# schematic-import-source.net
KiCad netlist of a schematic drawn in EasyEDA
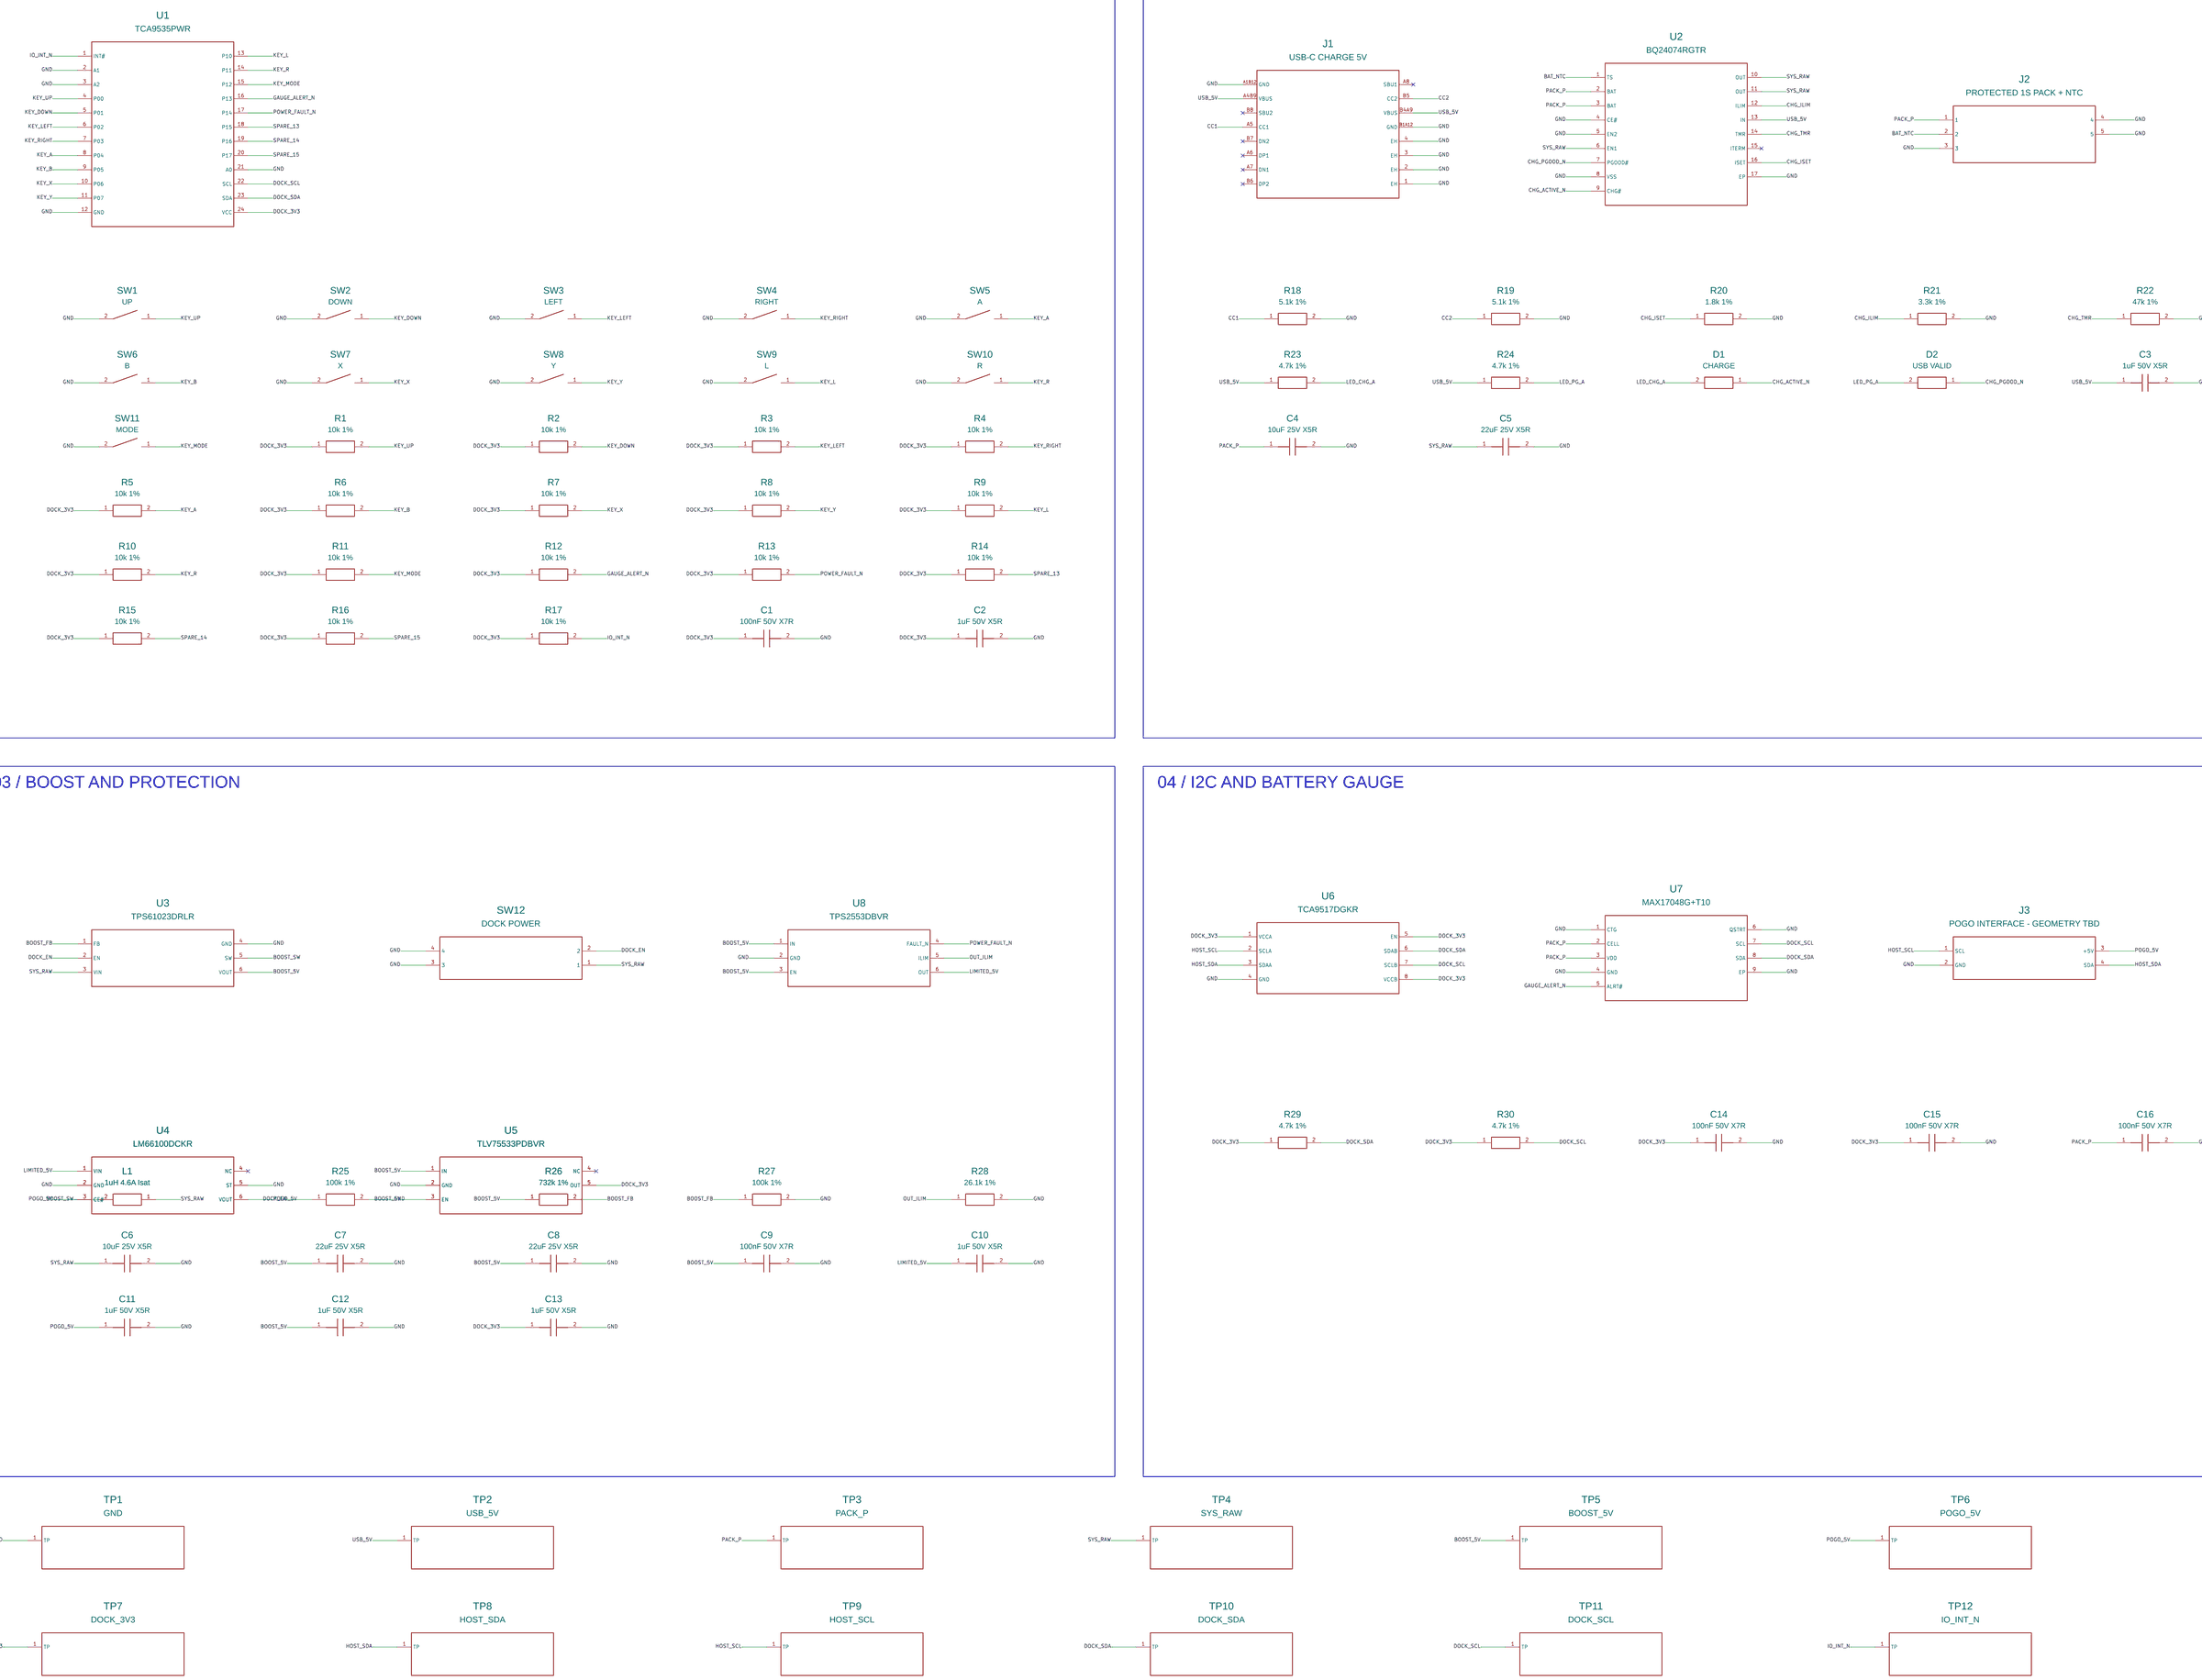
[diagram p0: schematic sheet]

(export (version "E")
  (design (tool "Eeschema 10.0.6"))
  (components
    (comp (ref "C1") (value "100nF 50V X7R") (libsource (lib "") (part "100nF 50V X7R")))
    (comp (ref "C2")
      (value "1uF 50V X5R")
      (fields
        (field (name "Manufacturer Part") "CL10A105KB8NNNC")
        (field (name "Manufacturer") "SAMSUNG(三星)")
      )
      (libsource (lib "") (part "1uF 50V X5R"))
    )
    (comp (ref "C3")
      (value "1uF 50V X5R")
      (fields
        (field (name "Manufacturer Part") "CL10A105KB8NNNC")
        (field (name "Manufacturer") "SAMSUNG(三星)")
      )
      (libsource (lib "") (part "1uF 50V X5R"))
    )
    (comp (ref "C4")
      (value "10uF 25V X5R")
      (fields
        (field (name "Manufacturer Part") "CL10A106MA8NRNC")
        (field (name "Manufacturer") "SAMSUNG(三星)")
      )
      (libsource (lib "") (part "10uF 25V X5R"))
    )
    (comp (ref "C5") (value "22uF 25V X5R") (libsource (lib "") (part "22uF 25V X5R")))
    (comp (ref "C6")
      (value "10uF 25V X5R")
      (fields
        (field (name "Manufacturer Part") "CL10A106MA8NRNC")
        (field (name "Manufacturer") "SAMSUNG(三星)")
      )
      (libsource (lib "") (part "10uF 25V X5R"))
    )
    (comp (ref "C7") (value "22uF 25V X5R") (libsource (lib "") (part "22uF 25V X5R")))
    (comp (ref "C8") (value "22uF 25V X5R") (libsource (lib "") (part "22uF 25V X5R")))
    (comp (ref "C9") (value "100nF 50V X7R") (libsource (lib "") (part "100nF 50V X7R")))
    (comp (ref "C10")
      (value "1uF 50V X5R")
      (fields
        (field (name "Manufacturer Part") "CL10A105KB8NNNC")
        (field (name "Manufacturer") "SAMSUNG(三星)")
      )
      (libsource (lib "") (part "1uF 50V X5R"))
    )
    (comp (ref "C11")
      (value "1uF 50V X5R")
      (fields
        (field (name "Manufacturer Part") "CL10A105KB8NNNC")
        (field (name "Manufacturer") "SAMSUNG(三星)")
      )
      (libsource (lib "") (part "1uF 50V X5R"))
    )
    (comp (ref "C12")
      (value "1uF 50V X5R")
      (fields
        (field (name "Manufacturer Part") "CL10A105KB8NNNC")
        (field (name "Manufacturer") "SAMSUNG(三星)")
      )
      (libsource (lib "") (part "1uF 50V X5R"))
    )
    (comp (ref "C13")
      (value "1uF 50V X5R")
      (fields
        (field (name "Manufacturer Part") "CL10A105KB8NNNC")
        (field (name "Manufacturer") "SAMSUNG(三星)")
      )
      (libsource (lib "") (part "1uF 50V X5R"))
    )
    (comp (ref "C14") (value "100nF 50V X7R") (libsource (lib "") (part "100nF 50V X7R")))
    (comp (ref "C15") (value "100nF 50V X7R") (libsource (lib "") (part "100nF 50V X7R")))
    (comp (ref "C16") (value "100nF 50V X7R") (libsource (lib "") (part "100nF 50V X7R")))
    (comp (ref "D1")
      (value "CHARGE")
      (fields (field (name "Manufacturer Part") "KT-0805黄灯") (field (name "Manufacturer") "KENTO"))
      (libsource (lib "") (part "CHARGE"))
    )
    (comp (ref "D2")
      (value "USB VALID")
      (fields (field (name "Manufacturer Part") "KT-0805黄灯") (field (name "Manufacturer") "KENTO"))
      (libsource (lib "") (part "USB VALID"))
    )
    (comp (ref "J1")
      (value "USB-C CHARGE 5V")
      (fields (field (name "Manufacturer Part") "TYPE-C-31-M-12") (field (name "Manufacturer") "韩国韩荣"))
      (libsource (lib "") (part "USB-C CHARGE 5V"))
    )
    (comp (ref "J2")
      (value "PROTECTED 1S PACK + NTC")
      (fields (field (name "Manufacturer Part") "B3B-PH-SM4-TB(LF)(SN)") (field (name "Manufacturer") "JST"))
      (libsource (lib "") (part "PROTECTED 1S PACK + NTC"))
    )
    (comp (ref "J3")
      (value "POGO INTERFACE - GEOMETRY TBD")
      (libsource (lib "") (part "POGO INTERFACE - GEOMETRY TBD"))
    )
    (comp (ref "L1")
      (value "1uH 4.6A Isat")
      (fields
        (field (name "Manufacturer Part") "FTC201610S1R0MBCA")
        (field (name "Manufacturer") "cjiang(长江微电)")
      )
      (libsource (lib "") (part "1uH 4.6A Isat"))
    )
    (comp (ref "R1")
      (value "10k 1%")
      (fields
        (field (name "Manufacturer Part") "0603WAF1002T5E")
        (field (name "Manufacturer") "UNI-ROYAL(厚声)")
      )
      (libsource (lib "") (part "10k 1%"))
    )
    (comp (ref "R2")
      (value "10k 1%")
      (fields
        (field (name "Manufacturer Part") "0603WAF1002T5E")
        (field (name "Manufacturer") "UNI-ROYAL(厚声)")
      )
      (libsource (lib "") (part "10k 1%"))
    )
    (comp (ref "R3")
      (value "10k 1%")
      (fields
        (field (name "Manufacturer Part") "0603WAF1002T5E")
        (field (name "Manufacturer") "UNI-ROYAL(厚声)")
      )
      (libsource (lib "") (part "10k 1%"))
    )
    (comp (ref "R4")
      (value "10k 1%")
      (fields
        (field (name "Manufacturer Part") "0603WAF1002T5E")
        (field (name "Manufacturer") "UNI-ROYAL(厚声)")
      )
      (libsource (lib "") (part "10k 1%"))
    )
    (comp (ref "R5")
      (value "10k 1%")
      (fields
        (field (name "Manufacturer Part") "0603WAF1002T5E")
        (field (name "Manufacturer") "UNI-ROYAL(厚声)")
      )
      (libsource (lib "") (part "10k 1%"))
    )
    (comp (ref "R6")
      (value "10k 1%")
      (fields
        (field (name "Manufacturer Part") "0603WAF1002T5E")
        (field (name "Manufacturer") "UNI-ROYAL(厚声)")
      )
      (libsource (lib "") (part "10k 1%"))
    )
    (comp (ref "R7")
      (value "10k 1%")
      (fields
        (field (name "Manufacturer Part") "0603WAF1002T5E")
        (field (name "Manufacturer") "UNI-ROYAL(厚声)")
      )
      (libsource (lib "") (part "10k 1%"))
    )
    (comp (ref "R8")
      (value "10k 1%")
      (fields
        (field (name "Manufacturer Part") "0603WAF1002T5E")
        (field (name "Manufacturer") "UNI-ROYAL(厚声)")
      )
      (libsource (lib "") (part "10k 1%"))
    )
    (comp (ref "R9")
      (value "10k 1%")
      (fields
        (field (name "Manufacturer Part") "0603WAF1002T5E")
        (field (name "Manufacturer") "UNI-ROYAL(厚声)")
      )
      (libsource (lib "") (part "10k 1%"))
    )
    (comp (ref "R10")
      (value "10k 1%")
      (fields
        (field (name "Manufacturer Part") "0603WAF1002T5E")
        (field (name "Manufacturer") "UNI-ROYAL(厚声)")
      )
      (libsource (lib "") (part "10k 1%"))
    )
    (comp (ref "R11")
      (value "10k 1%")
      (fields
        (field (name "Manufacturer Part") "0603WAF1002T5E")
        (field (name "Manufacturer") "UNI-ROYAL(厚声)")
      )
      (libsource (lib "") (part "10k 1%"))
    )
    (comp (ref "R12")
      (value "10k 1%")
      (fields
        (field (name "Manufacturer Part") "0603WAF1002T5E")
        (field (name "Manufacturer") "UNI-ROYAL(厚声)")
      )
      (libsource (lib "") (part "10k 1%"))
    )
    (comp (ref "R13")
      (value "10k 1%")
      (fields
        (field (name "Manufacturer Part") "0603WAF1002T5E")
        (field (name "Manufacturer") "UNI-ROYAL(厚声)")
      )
      (libsource (lib "") (part "10k 1%"))
    )
    (comp (ref "R14")
      (value "10k 1%")
      (fields
        (field (name "Manufacturer Part") "0603WAF1002T5E")
        (field (name "Manufacturer") "UNI-ROYAL(厚声)")
      )
      (libsource (lib "") (part "10k 1%"))
    )
    (comp (ref "R15")
      (value "10k 1%")
      (fields
        (field (name "Manufacturer Part") "0603WAF1002T5E")
        (field (name "Manufacturer") "UNI-ROYAL(厚声)")
      )
      (libsource (lib "") (part "10k 1%"))
    )
    (comp (ref "R16")
      (value "10k 1%")
      (fields
        (field (name "Manufacturer Part") "0603WAF1002T5E")
        (field (name "Manufacturer") "UNI-ROYAL(厚声)")
      )
      (libsource (lib "") (part "10k 1%"))
    )
    (comp (ref "R17")
      (value "10k 1%")
      (fields
        (field (name "Manufacturer Part") "0603WAF1002T5E")
        (field (name "Manufacturer") "UNI-ROYAL(厚声)")
      )
      (libsource (lib "") (part "10k 1%"))
    )
    (comp (ref "R18")
      (value "5.1k 1%")
      (fields
        (field (name "Manufacturer Part") "0603WAF5101T5E")
        (field (name "Manufacturer") "UNI-ROYAL(厚声)")
      )
      (libsource (lib "") (part "5.1k 1%"))
    )
    (comp (ref "R19")
      (value "5.1k 1%")
      (fields
        (field (name "Manufacturer Part") "0603WAF5101T5E")
        (field (name "Manufacturer") "UNI-ROYAL(厚声)")
      )
      (libsource (lib "") (part "5.1k 1%"))
    )
    (comp (ref "R20") (value "1.8k 1%") (libsource (lib "") (part "1.8k 1%")))
    (comp (ref "R21") (value "3.3k 1%") (libsource (lib "") (part "3.3k 1%")))
    (comp (ref "R22") (value "47k 1%") (libsource (lib "") (part "47k 1%")))
    (comp (ref "R23")
      (value "4.7k 1%")
      (fields
        (field (name "Manufacturer Part") "0603WAF4701T5E")
        (field (name "Manufacturer") "UNI-ROYAL(厚声)")
      )
      (libsource (lib "") (part "4.7k 1%"))
    )
    (comp (ref "R24")
      (value "4.7k 1%")
      (fields
        (field (name "Manufacturer Part") "0603WAF4701T5E")
        (field (name "Manufacturer") "UNI-ROYAL(厚声)")
      )
      (libsource (lib "") (part "4.7k 1%"))
    )
    (comp (ref "R25")
      (value "100k 1%")
      (fields
        (field (name "Manufacturer Part") "0603WAF1003T5E")
        (field (name "Manufacturer") "UNI-ROYAL(厚声)")
      )
      (libsource (lib "") (part "100k 1%"))
    )
    (comp (ref "R26") (value "732k 1%") (libsource (lib "") (part "732k 1%")))
    (comp (ref "R27")
      (value "100k 1%")
      (fields
        (field (name "Manufacturer Part") "0603WAF1003T5E")
        (field (name "Manufacturer") "UNI-ROYAL(厚声)")
      )
      (libsource (lib "") (part "100k 1%"))
    )
    (comp (ref "R28") (value "26.1k 1%") (libsource (lib "") (part "26.1k 1%")))
    (comp (ref "R29")
      (value "4.7k 1%")
      (fields
        (field (name "Manufacturer Part") "0603WAF4701T5E")
        (field (name "Manufacturer") "UNI-ROYAL(厚声)")
      )
      (libsource (lib "") (part "4.7k 1%"))
    )
    (comp (ref "R30")
      (value "4.7k 1%")
      (fields
        (field (name "Manufacturer Part") "0603WAF4701T5E")
        (field (name "Manufacturer") "UNI-ROYAL(厚声)")
      )
      (libsource (lib "") (part "4.7k 1%"))
    )
    (comp (ref "SW1")
      (value "UP")
      (fields (field (name "Manufacturer Part") "TS-1088-AR02016") (field (name "Manufacturer") "XUNPU(讯普)"))
      (libsource (lib "") (part "UP"))
    )
    (comp (ref "SW2")
      (value "DOWN")
      (fields (field (name "Manufacturer Part") "TS-1088-AR02016") (field (name "Manufacturer") "XUNPU(讯普)"))
      (libsource (lib "") (part "DOWN"))
    )
    (comp (ref "SW3")
      (value "LEFT")
      (fields (field (name "Manufacturer Part") "TS-1088-AR02016") (field (name "Manufacturer") "XUNPU(讯普)"))
      (libsource (lib "") (part "LEFT"))
    )
    (comp (ref "SW4")
      (value "RIGHT")
      (fields (field (name "Manufacturer Part") "TS-1088-AR02016") (field (name "Manufacturer") "XUNPU(讯普)"))
      (libsource (lib "") (part "RIGHT"))
    )
    (comp (ref "SW5")
      (value "A")
      (fields (field (name "Manufacturer Part") "TS-1088-AR02016") (field (name "Manufacturer") "XUNPU(讯普)"))
      (libsource (lib "") (part "A"))
    )
    (comp (ref "SW6")
      (value "B")
      (fields (field (name "Manufacturer Part") "TS-1088-AR02016") (field (name "Manufacturer") "XUNPU(讯普)"))
      (libsource (lib "") (part "B"))
    )
    (comp (ref "SW7")
      (value "X")
      (fields (field (name "Manufacturer Part") "TS-1088-AR02016") (field (name "Manufacturer") "XUNPU(讯普)"))
      (libsource (lib "") (part "X"))
    )
    (comp (ref "SW8")
      (value "Y")
      (fields (field (name "Manufacturer Part") "TS-1088-AR02016") (field (name "Manufacturer") "XUNPU(讯普)"))
      (libsource (lib "") (part "Y"))
    )
    (comp (ref "SW9")
      (value "L")
      (fields (field (name "Manufacturer Part") "TS-1088-AR02016") (field (name "Manufacturer") "XUNPU(讯普)"))
      (libsource (lib "") (part "L"))
    )
    (comp (ref "SW10")
      (value "R")
      (fields (field (name "Manufacturer Part") "TS-1088-AR02016") (field (name "Manufacturer") "XUNPU(讯普)"))
      (libsource (lib "") (part "R"))
    )
    (comp (ref "SW11")
      (value "MODE")
      (fields (field (name "Manufacturer Part") "TS-1088-AR02016") (field (name "Manufacturer") "XUNPU(讯普)"))
      (libsource (lib "") (part "MODE"))
    )
    (comp (ref "SW12")
      (value "DOCK POWER")
      (fields (field (name "Manufacturer Part") "MSK12C02") (field (name "Manufacturer") "SHOU HAN(首韩)"))
      (libsource (lib "") (part "DOCK POWER"))
    )
    (comp (ref "TP1") (value "GND") (libsource (lib "") (part "GND")))
    (comp (ref "TP2") (value "USB_5V") (libsource (lib "") (part "USB_5V")))
    (comp (ref "TP3") (value "PACK_P") (libsource (lib "") (part "PACK_P")))
    (comp (ref "TP4") (value "SYS_RAW") (libsource (lib "") (part "SYS_RAW")))
    (comp (ref "TP5") (value "BOOST_5V") (libsource (lib "") (part "BOOST_5V")))
    (comp (ref "TP6") (value "POGO_5V") (libsource (lib "") (part "POGO_5V")))
    (comp (ref "TP7") (value "DOCK_3V3") (libsource (lib "") (part "DOCK_3V3")))
    (comp (ref "TP8") (value "HOST_SDA") (libsource (lib "") (part "HOST_SDA")))
    (comp (ref "TP9") (value "HOST_SCL") (libsource (lib "") (part "HOST_SCL")))
    (comp (ref "TP10") (value "DOCK_SDA") (libsource (lib "") (part "DOCK_SDA")))
    (comp (ref "TP11") (value "DOCK_SCL") (libsource (lib "") (part "DOCK_SCL")))
    (comp (ref "TP12") (value "IO_INT_N") (libsource (lib "") (part "IO_INT_N")))
    (comp (ref "U1")
      (value "TCA9535PWR")
      (fields (field (name "Manufacturer") "TI(德州仪器)"))
      (libsource (lib "") (part "TCA9535PWR"))
    )
    (comp (ref "U2")
      (value "BQ24074RGTR")
      (fields (field (name "Manufacturer") "TI(德州仪器)"))
      (libsource (lib "") (part "BQ24074RGTR"))
    )
    (comp (ref "U3")
      (value "TPS61023DRLR")
      (fields (field (name "Manufacturer") "TI(德州仪器)"))
      (libsource (lib "") (part "TPS61023DRLR"))
    )
    (comp (ref "U4")
      (value "LM66100DCKR")
      (fields (field (name "Manufacturer") "TI(德州仪器)"))
      (libsource (lib "") (part "LM66100DCKR"))
    )
    (comp (ref "U5")
      (value "TLV75533PDBVR")
      (fields (field (name "Manufacturer") "TI(德州仪器)"))
      (libsource (lib "") (part "TLV75533PDBVR"))
    )
    (comp (ref "U6")
      (value "TCA9517DGKR")
      (fields (field (name "Manufacturer") "TI(德州仪器)"))
      (libsource (lib "") (part "TCA9517DGKR"))
    )
    (comp (ref "U7")
      (value "MAX17048G+T10")
      (fields (field (name "Manufacturer") "ADI(亚德诺)/MAXIM(美信)"))
      (libsource (lib "") (part "MAX17048G+T10"))
    )
    (comp (ref "U8") (value "TPS2553DBVR") (libsource (lib "") (part "TPS2553DBVR")))
  )
  (nets
    (net (code "1") (name "/BAT_NTC") (class "Default")
      (node (ref "J2") (pin "2") (pinfunction "2_2") (pintype "unspecified"))
      (node (ref "U2") (pin "1") (pinfunction "TS_1") (pintype "unspecified"))
    )
    (net (code "2") (name "/BOOST_5V") (class "Default")
      (node (ref "C12") (pin "1") (pintype "unspecified"))
      (node (ref "C7") (pin "1") (pintype "unspecified"))
      (node (ref "C8") (pin "1") (pintype "unspecified"))
      (node (ref "C9") (pin "1") (pintype "unspecified"))
      (node (ref "R26") (pin "1") (pintype "unspecified"))
      (node (ref "TP5") (pin "1") (pinfunction "TP_1") (pintype "unspecified"))
      (node (ref "U3") (pin "6") (pinfunction "VOUT_6") (pintype "unspecified"))
      (node (ref "U5") (pin "1") (pinfunction "IN_1") (pintype "unspecified"))
      (node (ref "U5") (pin "3") (pinfunction "EN_3") (pintype "unspecified"))
      (node (ref "U8") (pin "1") (pinfunction "IN_1") (pintype "unspecified"))
      (node (ref "U8") (pin "3") (pinfunction "EN_3") (pintype "unspecified"))
    )
    (net (code "3") (name "/BOOST_FB") (class "Default")
      (node (ref "R26") (pin "2") (pintype "unspecified"))
      (node (ref "R27") (pin "1") (pintype "unspecified"))
      (node (ref "U3") (pin "1") (pinfunction "FB_1") (pintype "unspecified"))
    )
    (net (code "4") (name "/BOOST_SW") (class "Default")
      (node (ref "C11") (pin "1") (pintype "unspecified"))
      (node (ref "J3") (pin "3") (pinfunction "+5V_3") (pintype "unspecified"))
      (node (ref "L1") (pin "2") (pintype "unspecified"))
      (node (ref "TP6") (pin "1") (pinfunction "TP_1") (pintype "unspecified"))
      (node (ref "U3") (pin "5") (pinfunction "SW_5") (pintype "unspecified"))
      (node (ref "U4") (pin "3") (pinfunction "CE#_3") (pintype "unspecified"))
      (node (ref "U4") (pin "6") (pinfunction "VOUT_6") (pintype "unspecified"))
    )
    (net (code "5") (name "/CC1") (class "Default")
      (node (ref "J1") (pin "A5") (pinfunction "CC1_A5") (pintype "unspecified"))
      (node (ref "R18") (pin "1") (pintype "unspecified"))
    )
    (net (code "6") (name "/CC2") (class "Default")
      (node (ref "J1") (pin "B5") (pinfunction "CC2_B5") (pintype "unspecified"))
      (node (ref "R19") (pin "1") (pintype "unspecified"))
    )
    (net (code "7") (name "/CHG_ACTIVE_N") (class "Default")
      (node (ref "D1") (pin "1") (pintype "unspecified"))
      (node (ref "U2") (pin "9") (pinfunction "CHG#_9") (pintype "unspecified"))
    )
    (net (code "8") (name "/CHG_ILIM") (class "Default")
      (node (ref "R21") (pin "1") (pintype "unspecified"))
      (node (ref "U2") (pin "12") (pinfunction "ILIM_12") (pintype "unspecified"))
    )
    (net (code "9") (name "/CHG_ISET") (class "Default")
      (node (ref "R20") (pin "1") (pintype "unspecified"))
      (node (ref "U2") (pin "16") (pinfunction "ISET_16") (pintype "unspecified"))
    )
    (net (code "10") (name "/CHG_PGOOD_N") (class "Default")
      (node (ref "D2") (pin "1") (pintype "unspecified"))
      (node (ref "U2") (pin "7") (pinfunction "PGOOD#_7") (pintype "unspecified"))
    )
    (net (code "11") (name "/CHG_TMR") (class "Default")
      (node (ref "R22") (pin "1") (pintype "unspecified"))
      (node (ref "U2") (pin "14") (pinfunction "TMR_14") (pintype "unspecified"))
    )
    (net (code "12") (name "/DOCK_3V3") (class "Default")
      (node (ref "C1") (pin "1") (pintype "unspecified"))
      (node (ref "C13") (pin "1") (pintype "unspecified"))
      (node (ref "C14") (pin "1") (pintype "unspecified"))
      (node (ref "C15") (pin "1") (pintype "unspecified"))
      (node (ref "C2") (pin "1") (pintype "unspecified"))
      (node (ref "R1") (pin "1") (pintype "unspecified"))
      (node (ref "R10") (pin "1") (pintype "unspecified"))
      (node (ref "R11") (pin "1") (pintype "unspecified"))
      (node (ref "R12") (pin "1") (pintype "unspecified"))
      (node (ref "R13") (pin "1") (pintype "unspecified"))
      (node (ref "R14") (pin "1") (pintype "unspecified"))
      (node (ref "R15") (pin "1") (pintype "unspecified"))
      (node (ref "R16") (pin "1") (pintype "unspecified"))
      (node (ref "R17") (pin "1") (pintype "unspecified"))
      (node (ref "R2") (pin "1") (pintype "unspecified"))
      (node (ref "R29") (pin "1") (pintype "unspecified"))
      (node (ref "R3") (pin "1") (pintype "unspecified"))
      (node (ref "R30") (pin "1") (pintype "unspecified"))
      (node (ref "R4") (pin "1") (pintype "unspecified"))
      (node (ref "R5") (pin "1") (pintype "unspecified"))
      (node (ref "R6") (pin "1") (pintype "unspecified"))
      (node (ref "R7") (pin "1") (pintype "unspecified"))
      (node (ref "R8") (pin "1") (pintype "unspecified"))
      (node (ref "R9") (pin "1") (pintype "unspecified"))
      (node (ref "TP7") (pin "1") (pinfunction "TP_1") (pintype "unspecified"))
      (node (ref "U1") (pin "24") (pinfunction "VCC_24") (pintype "unspecified"))
      (node (ref "U5") (pin "5") (pinfunction "OUT_5") (pintype "unspecified"))
      (node (ref "U6") (pin "1") (pinfunction "VCCA_1") (pintype "unspecified"))
      (node (ref "U6") (pin "5") (pinfunction "EN_5") (pintype "unspecified"))
      (node (ref "U6") (pin "8") (pinfunction "VCCB_8") (pintype "unspecified"))
    )
    (net (code "13") (name "/DOCK_EN") (class "Default")
      (node (ref "R25") (pin "1") (pintype "unspecified"))
      (node (ref "SW12") (pin "2") (pinfunction "2_2") (pintype "unspecified"))
      (node (ref "U3") (pin "2") (pinfunction "EN_2") (pintype "unspecified"))
    )
    (net (code "14") (name "/DOCK_SCL") (class "Default")
      (node (ref "R30") (pin "2") (pintype "unspecified"))
      (node (ref "TP11") (pin "1") (pinfunction "TP_1") (pintype "unspecified"))
      (node (ref "U1") (pin "22") (pinfunction "SCL_22") (pintype "unspecified"))
      (node (ref "U6") (pin "7") (pinfunction "SCLB_7") (pintype "unspecified"))
      (node (ref "U7") (pin "7") (pinfunction "SCL_7") (pintype "unspecified"))
    )
    (net (code "15") (name "/DOCK_SDA") (class "Default")
      (node (ref "R29") (pin "2") (pintype "unspecified"))
      (node (ref "TP10") (pin "1") (pinfunction "TP_1") (pintype "unspecified"))
      (node (ref "U1") (pin "23") (pinfunction "SDA_23") (pintype "unspecified"))
      (node (ref "U6") (pin "6") (pinfunction "SDAB_6") (pintype "unspecified"))
      (node (ref "U7") (pin "8") (pinfunction "SDA_8") (pintype "unspecified"))
    )
    (net (code "16") (name "/GAUGE_ALERT_N") (class "Default")
      (node (ref "R12") (pin "2") (pintype "unspecified"))
      (node (ref "U1") (pin "16") (pinfunction "P13_16") (pintype "unspecified"))
      (node (ref "U7") (pin "5") (pinfunction "ALRT#_5") (pintype "unspecified"))
    )
    (net (code "17") (name "/GND") (class "Default")
      (node (ref "C1") (pin "2") (pintype "unspecified"))
      (node (ref "C10") (pin "2") (pintype "unspecified"))
      (node (ref "C11") (pin "2") (pintype "unspecified"))
      (node (ref "C12") (pin "2") (pintype "unspecified"))
      (node (ref "C13") (pin "2") (pintype "unspecified"))
      (node (ref "C14") (pin "2") (pintype "unspecified"))
      (node (ref "C15") (pin "2") (pintype "unspecified"))
      (node (ref "C16") (pin "2") (pintype "unspecified"))
      (node (ref "C2") (pin "2") (pintype "unspecified"))
      (node (ref "C3") (pin "2") (pintype "unspecified"))
      (node (ref "C4") (pin "2") (pintype "unspecified"))
      (node (ref "C5") (pin "2") (pintype "unspecified"))
      (node (ref "C6") (pin "2") (pintype "unspecified"))
      (node (ref "C7") (pin "2") (pintype "unspecified"))
      (node (ref "C8") (pin "2") (pintype "unspecified"))
      (node (ref "C9") (pin "2") (pintype "unspecified"))
      (node (ref "J1") (pin "1") (pinfunction "EH_1") (pintype "unspecified"))
      (node (ref "J1") (pin "2") (pinfunction "EH_2") (pintype "unspecified"))
      (node (ref "J1") (pin "3") (pinfunction "EH_3") (pintype "unspecified"))
      (node (ref "J1") (pin "4") (pinfunction "EH_4") (pintype "unspecified"))
      (node (ref "J1") (pin "A1B12") (pinfunction "GND_A1B12") (pintype "unspecified"))
      (node (ref "J1") (pin "B1A12") (pinfunction "GND_B1A12") (pintype "unspecified"))
      (node (ref "J2") (pin "3") (pinfunction "3_3") (pintype "unspecified"))
      (node (ref "J2") (pin "4") (pinfunction "4_4") (pintype "unspecified"))
      (node (ref "J2") (pin "5") (pinfunction "5_5") (pintype "unspecified"))
      (node (ref "J3") (pin "2") (pinfunction "GND_2") (pintype "unspecified"))
      (node (ref "R18") (pin "2") (pintype "unspecified"))
      (node (ref "R19") (pin "2") (pintype "unspecified"))
      (node (ref "R20") (pin "2") (pintype "unspecified"))
      (node (ref "R21") (pin "2") (pintype "unspecified"))
      (node (ref "R22") (pin "2") (pintype "unspecified"))
      (node (ref "R25") (pin "2") (pintype "unspecified"))
      (node (ref "R27") (pin "2") (pintype "unspecified"))
      (node (ref "R28") (pin "2") (pintype "unspecified"))
      (node (ref "SW1") (pin "2") (pintype "unspecified"))
      (node (ref "SW10") (pin "2") (pintype "unspecified"))
      (node (ref "SW11") (pin "2") (pintype "unspecified"))
      (node (ref "SW12") (pin "3") (pinfunction "3_3") (pintype "unspecified"))
      (node (ref "SW12") (pin "4") (pinfunction "4_4") (pintype "unspecified"))
      (node (ref "SW2") (pin "2") (pintype "unspecified"))
      (node (ref "SW3") (pin "2") (pintype "unspecified"))
      (node (ref "SW4") (pin "2") (pintype "unspecified"))
      (node (ref "SW5") (pin "2") (pintype "unspecified"))
      (node (ref "SW6") (pin "2") (pintype "unspecified"))
      (node (ref "SW7") (pin "2") (pintype "unspecified"))
      (node (ref "SW8") (pin "2") (pintype "unspecified"))
      (node (ref "SW9") (pin "2") (pintype "unspecified"))
      (node (ref "TP1") (pin "1") (pinfunction "TP_1") (pintype "unspecified"))
      (node (ref "U1") (pin "12") (pinfunction "GND_12") (pintype "unspecified"))
      (node (ref "U1") (pin "2") (pinfunction "A1_2") (pintype "unspecified"))
      (node (ref "U1") (pin "21") (pinfunction "A0_21") (pintype "unspecified"))
      (node (ref "U1") (pin "3") (pinfunction "A2_3") (pintype "unspecified"))
      (node (ref "U2") (pin "17") (pinfunction "EP_17") (pintype "unspecified"))
      (node (ref "U2") (pin "4") (pinfunction "CE#_4") (pintype "unspecified"))
      (node (ref "U2") (pin "5") (pinfunction "EN2_5") (pintype "unspecified"))
      (node (ref "U2") (pin "8") (pinfunction "VSS_8") (pintype "unspecified"))
      (node (ref "U3") (pin "4") (pinfunction "GND_4") (pintype "unspecified"))
      (node (ref "U4") (pin "2") (pinfunction "GND_2") (pintype "unspecified"))
      (node (ref "U4") (pin "5") (pinfunction "ST_5") (pintype "unspecified"))
      (node (ref "U5") (pin "2") (pinfunction "GND_2") (pintype "unspecified"))
      (node (ref "U6") (pin "4") (pinfunction "GND_4") (pintype "unspecified"))
      (node (ref "U7") (pin "1") (pinfunction "CTG_1") (pintype "unspecified"))
      (node (ref "U7") (pin "4") (pinfunction "GND_4") (pintype "unspecified"))
      (node (ref "U7") (pin "6") (pinfunction "QSTRT_6") (pintype "unspecified"))
      (node (ref "U7") (pin "9") (pinfunction "EP_9") (pintype "unspecified"))
      (node (ref "U8") (pin "2") (pinfunction "GND_2") (pintype "unspecified"))
    )
    (net (code "18") (name "/HOST_SCL") (class "Default")
      (node (ref "J3") (pin "1") (pinfunction "SCL_1") (pintype "unspecified"))
      (node (ref "TP9") (pin "1") (pinfunction "TP_1") (pintype "unspecified"))
      (node (ref "U6") (pin "2") (pinfunction "SCLA_2") (pintype "unspecified"))
    )
    (net (code "19") (name "/HOST_SDA") (class "Default")
      (node (ref "J3") (pin "4") (pinfunction "SDA_4") (pintype "unspecified"))
      (node (ref "TP8") (pin "1") (pinfunction "TP_1") (pintype "unspecified"))
      (node (ref "U6") (pin "3") (pinfunction "SDAA_3") (pintype "unspecified"))
    )
    (net (code "20") (name "/IO_INT_N") (class "Default")
      (node (ref "R17") (pin "2") (pintype "unspecified"))
      (node (ref "TP12") (pin "1") (pinfunction "TP_1") (pintype "unspecified"))
      (node (ref "U1") (pin "1") (pinfunction "INT#_1") (pintype "unspecified"))
    )
    (net (code "21") (name "/KEY_A") (class "Default")
      (node (ref "R5") (pin "2") (pintype "unspecified"))
      (node (ref "SW5") (pin "1") (pintype "unspecified"))
      (node (ref "U1") (pin "8") (pinfunction "P04_8") (pintype "unspecified"))
    )
    (net (code "22") (name "/KEY_B") (class "Default")
      (node (ref "R6") (pin "2") (pintype "unspecified"))
      (node (ref "SW6") (pin "1") (pintype "unspecified"))
      (node (ref "U1") (pin "9") (pinfunction "P05_9") (pintype "unspecified"))
    )
    (net (code "23") (name "/KEY_DOWN") (class "Default")
      (node (ref "R2") (pin "2") (pintype "unspecified"))
      (node (ref "SW2") (pin "1") (pintype "unspecified"))
      (node (ref "U1") (pin "5") (pinfunction "P01_5") (pintype "unspecified"))
    )
    (net (code "24") (name "/KEY_L") (class "Default")
      (node (ref "R9") (pin "2") (pintype "unspecified"))
      (node (ref "SW9") (pin "1") (pintype "unspecified"))
      (node (ref "U1") (pin "13") (pinfunction "P10_13") (pintype "unspecified"))
    )
    (net (code "25") (name "/KEY_LEFT") (class "Default")
      (node (ref "R3") (pin "2") (pintype "unspecified"))
      (node (ref "SW3") (pin "1") (pintype "unspecified"))
      (node (ref "U1") (pin "6") (pinfunction "P02_6") (pintype "unspecified"))
    )
    (net (code "26") (name "/KEY_MODE") (class "Default")
      (node (ref "R11") (pin "2") (pintype "unspecified"))
      (node (ref "SW11") (pin "1") (pintype "unspecified"))
      (node (ref "U1") (pin "15") (pinfunction "P12_15") (pintype "unspecified"))
    )
    (net (code "27") (name "/KEY_R") (class "Default")
      (node (ref "R10") (pin "2") (pintype "unspecified"))
      (node (ref "SW10") (pin "1") (pintype "unspecified"))
      (node (ref "U1") (pin "14") (pinfunction "P11_14") (pintype "unspecified"))
    )
    (net (code "28") (name "/KEY_RIGHT") (class "Default")
      (node (ref "R4") (pin "2") (pintype "unspecified"))
      (node (ref "SW4") (pin "1") (pintype "unspecified"))
      (node (ref "U1") (pin "7") (pinfunction "P03_7") (pintype "unspecified"))
    )
    (net (code "29") (name "/KEY_UP") (class "Default")
      (node (ref "R1") (pin "2") (pintype "unspecified"))
      (node (ref "SW1") (pin "1") (pintype "unspecified"))
      (node (ref "U1") (pin "4") (pinfunction "P00_4") (pintype "unspecified"))
    )
    (net (code "30") (name "/KEY_X") (class "Default")
      (node (ref "R7") (pin "2") (pintype "unspecified"))
      (node (ref "SW7") (pin "1") (pintype "unspecified"))
      (node (ref "U1") (pin "10") (pinfunction "P06_10") (pintype "unspecified"))
    )
    (net (code "31") (name "/KEY_Y") (class "Default")
      (node (ref "R8") (pin "2") (pintype "unspecified"))
      (node (ref "SW8") (pin "1") (pintype "unspecified"))
      (node (ref "U1") (pin "11") (pinfunction "P07_11") (pintype "unspecified"))
    )
    (net (code "32") (name "/LED_CHG_A") (class "Default")
      (node (ref "D1") (pin "2") (pintype "unspecified"))
      (node (ref "R23") (pin "2") (pintype "unspecified"))
    )
    (net (code "33") (name "/LED_PG_A") (class "Default")
      (node (ref "D2") (pin "2") (pintype "unspecified"))
      (node (ref "R24") (pin "2") (pintype "unspecified"))
    )
    (net (code "34") (name "/LIMITED_5V") (class "Default")
      (node (ref "C10") (pin "1") (pintype "unspecified"))
      (node (ref "U4") (pin "1") (pinfunction "VIN_1") (pintype "unspecified"))
      (node (ref "U8") (pin "6") (pinfunction "OUT_6") (pintype "unspecified"))
    )
    (net (code "35") (name "/OUT_ILIM") (class "Default")
      (node (ref "R28") (pin "1") (pintype "unspecified"))
      (node (ref "U8") (pin "5") (pinfunction "ILIM_5") (pintype "unspecified"))
    )
    (net (code "36") (name "/PACK_P") (class "Default")
      (node (ref "C16") (pin "1") (pintype "unspecified"))
      (node (ref "C4") (pin "1") (pintype "unspecified"))
      (node (ref "J2") (pin "1") (pinfunction "1_1") (pintype "unspecified"))
      (node (ref "TP3") (pin "1") (pinfunction "TP_1") (pintype "unspecified"))
      (node (ref "U2") (pin "2") (pinfunction "BAT_2") (pintype "unspecified"))
      (node (ref "U2") (pin "3") (pinfunction "BAT_3") (pintype "unspecified"))
      (node (ref "U7") (pin "2") (pinfunction "CELL_2") (pintype "unspecified"))
      (node (ref "U7") (pin "3") (pinfunction "VDD_3") (pintype "unspecified"))
    )
    (net (code "37") (name "/POWER_FAULT_N") (class "Default")
      (node (ref "R13") (pin "2") (pintype "unspecified"))
      (node (ref "U1") (pin "17") (pinfunction "P14_17") (pintype "unspecified"))
      (node (ref "U8") (pin "4") (pinfunction "FAULT_N_4") (pintype "unspecified"))
    )
    (net (code "38") (name "/SPARE_13") (class "Default")
      (node (ref "R14") (pin "2") (pintype "unspecified"))
      (node (ref "U1") (pin "18") (pinfunction "P15_18") (pintype "unspecified"))
    )
    (net (code "39") (name "/SPARE_14") (class "Default")
      (node (ref "R15") (pin "2") (pintype "unspecified"))
      (node (ref "U1") (pin "19") (pinfunction "P16_19") (pintype "unspecified"))
    )
    (net (code "40") (name "/SPARE_15") (class "Default")
      (node (ref "R16") (pin "2") (pintype "unspecified"))
      (node (ref "U1") (pin "20") (pinfunction "P17_20") (pintype "unspecified"))
    )
    (net (code "41") (name "/SYS_RAW") (class "Default")
      (node (ref "C5") (pin "1") (pintype "unspecified"))
      (node (ref "C6") (pin "1") (pintype "unspecified"))
      (node (ref "L1") (pin "1") (pintype "unspecified"))
      (node (ref "SW12") (pin "1") (pinfunction "1_1") (pintype "unspecified"))
      (node (ref "TP4") (pin "1") (pinfunction "TP_1") (pintype "unspecified"))
      (node (ref "U2") (pin "10") (pinfunction "OUT_10") (pintype "unspecified"))
      (node (ref "U2") (pin "11") (pinfunction "OUT_11") (pintype "unspecified"))
      (node (ref "U2") (pin "6") (pinfunction "EN1_6") (pintype "unspecified"))
      (node (ref "U3") (pin "3") (pinfunction "VIN_3") (pintype "unspecified"))
    )
    (net (code "42") (name "/USB_5V") (class "Default")
      (node (ref "C3") (pin "1") (pintype "unspecified"))
      (node (ref "J1") (pin "A4B9") (pinfunction "VBUS_A4B9") (pintype "unspecified"))
      (node (ref "J1") (pin "B4A9") (pinfunction "VBUS_B4A9") (pintype "unspecified"))
      (node (ref "R23") (pin "1") (pintype "unspecified"))
      (node (ref "R24") (pin "1") (pintype "unspecified"))
      (node (ref "TP2") (pin "1") (pinfunction "TP_1") (pintype "unspecified"))
      (node (ref "U2") (pin "13") (pinfunction "IN_13") (pintype "unspecified"))
    )
    (net (code "43") (name "unconnected-(J1-DN1-PadA7)") (class "Default")
      (node (ref "J1") (pin "A7") (pinfunction "DN1_A7") (pintype "unspecified+no_connect"))
    )
    (net (code "44") (name "unconnected-(J1-DN2-PadB7)") (class "Default")
      (node (ref "J1") (pin "B7") (pinfunction "DN2_B7") (pintype "unspecified+no_connect"))
    )
    (net (code "45") (name "unconnected-(J1-DP1-PadA6)") (class "Default")
      (node (ref "J1") (pin "A6") (pinfunction "DP1_A6") (pintype "unspecified+no_connect"))
    )
    (net (code "46") (name "unconnected-(J1-DP2-PadB6)") (class "Default")
      (node (ref "J1") (pin "B6") (pinfunction "DP2_B6") (pintype "unspecified+no_connect"))
    )
    (net (code "47") (name "unconnected-(J1-SBU1-PadA8)") (class "Default")
      (node (ref "J1") (pin "A8") (pinfunction "SBU1_A8") (pintype "unspecified+no_connect"))
    )
    (net (code "48") (name "unconnected-(J1-SBU2-PadB8)") (class "Default")
      (node (ref "J1") (pin "B8") (pinfunction "SBU2_B8") (pintype "unspecified+no_connect"))
    )
    (net (code "49") (name "unconnected-(U2-ITERM-Pad15)") (class "Default")
      (node (ref "U2") (pin "15") (pinfunction "ITERM_15") (pintype "unspecified+no_connect"))
    )
    (net (code "50") (name "unconnected-(U4-NC-Pad4)") (class "Default")
      (node (ref "U4") (pin "4") (pinfunction "NC_4") (pintype "unspecified+no_connect"))
    )
    (net (code "51") (name "unconnected-(U5-NC-Pad4)") (class "Default")
      (node (ref "U5") (pin "4") (pinfunction "NC_4") (pintype "unspecified+no_connect"))
    )
  )
)
